# modFOC-Sensing.net
KiCad netlist of a schematic drawn in Altium Designer
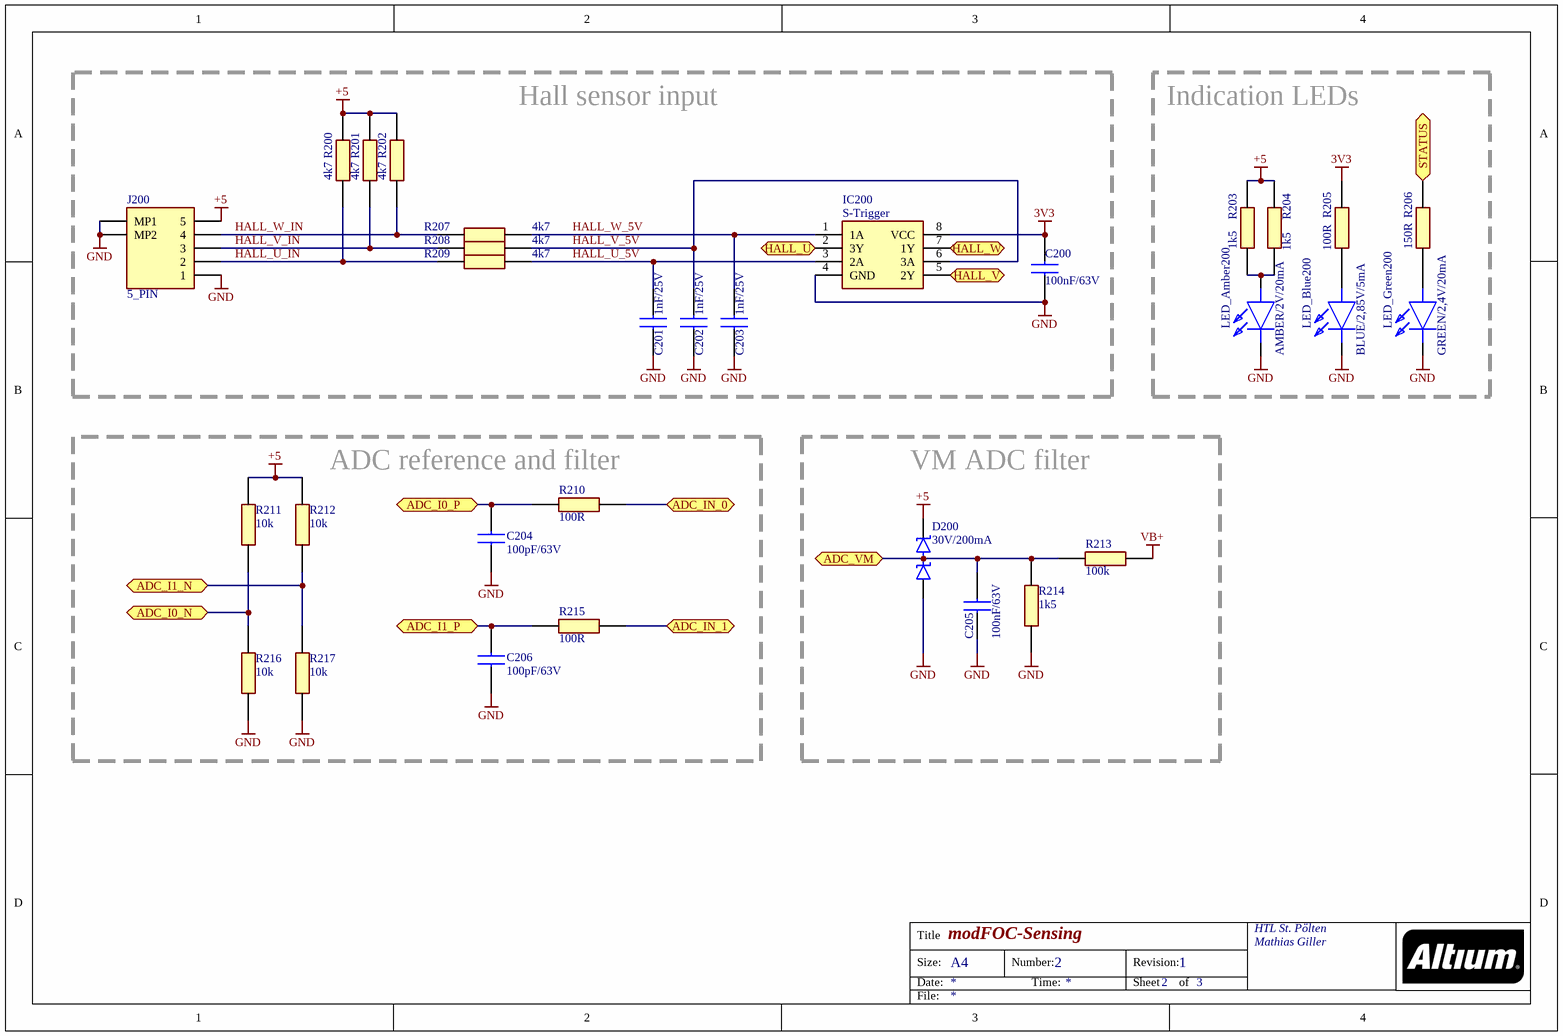
[diagram p0: modFOC-Sensing.SchDoc]

(export (version "E")
  (design (tool "Eeschema 10.0.6"))
  (components
    (comp (ref "C200")
      (value "100nF/63V")
      (footprint "CAPC1608X97N")
      (description "Capacitor")
      (fields
        (field (name "MANUFACTURER_PART_NUMBER") "VJ0603Y104JXJAC")
        (field (name "MOUSER PART NUMBER") "77-VJ0603Y104JXJAC")
      )
      (libsource (lib "Schlib1") (part "C0805C104MMREC7210"))
    )
    (comp (ref "C201")
      (value "1nF/25V")
      (footprint "CAPC1608X97N")
      (description "Capacitor")
      (fields
        (field (name "MANUFACTURER_PART_NUMBER") "GRM033R71E102KA01D")
        (field (name "MOUSER PART NUMBER") "81-GRM033R71E102KA1D")
      )
      (libsource (lib "Schlib1") (part "GRM033R71E102KA01D"))
    )
    (comp (ref "C202")
      (value "1nF/25V")
      (footprint "CAPC1608X97N")
      (description "Capacitor")
      (fields
        (field (name "MANUFACTURER_PART_NUMBER") "GRM033R71E102KA01D")
        (field (name "MOUSER PART NUMBER") "81-GRM033R71E102KA1D")
      )
      (libsource (lib "Schlib1") (part "GRM033R71E102KA01D"))
    )
    (comp (ref "C203")
      (value "1nF/25V")
      (footprint "CAPC1608X97N")
      (description "Capacitor")
      (fields
        (field (name "MANUFACTURER_PART_NUMBER") "GRM033R71E102KA01D")
        (field (name "MOUSER PART NUMBER") "81-GRM033R71E102KA1D")
      )
      (libsource (lib "Schlib1") (part "GRM033R71E102KA01D"))
    )
    (comp (ref "C204")
      (value "100pF/63V")
      (footprint "CAPC1608X87N")
      (description "Capacitor")
      (fields
        (field (name "MANUFACTURER_PART_NUMBER") "C0603C101K1HACTU")
        (field (name "MOUSER PART NUMBER") "80-C0603C101K1HACTU")
      )
      (libsource (lib "Schlib1") (part "C0603C101K1HACTU"))
    )
    (comp (ref "C205")
      (value "100nF/63V")
      (footprint "CAPC1608X97N")
      (description "Capacitor")
      (fields
        (field (name "MANUFACTURER_PART_NUMBER") "VJ0603Y104JXJAC")
        (field (name "MOUSER PART NUMBER") "77-VJ0603Y104JXJAC")
      )
      (libsource (lib "Schlib1") (part "C0805C104MMREC7210"))
    )
    (comp (ref "C206")
      (value "100pF/63V")
      (footprint "CAPC1608X87N")
      (description "Capacitor")
      (fields
        (field (name "MANUFACTURER_PART_NUMBER") "C0603C101K1HACTU")
        (field (name "MOUSER PART NUMBER") "80-C0603C101K1HACTU")
      )
      (libsource (lib "Schlib1") (part "C0603C101K1HACTU"))
    )
    (comp (ref "D200")
      (value "30V/200mA")
      (footprint "SOT95P240X110-3N")
      (description "Schottky Diode")
      (fields
        (field (name "MANUFACTURER_PART_NUMBER") "BAT54S")
        (field (name "MOUSER PART NUMBER") "583-BAT54S")
      )
      (libsource (lib "Schlib1") (part "BAT54S"))
    )
    (comp (ref "IC200")
      (value "S-Trigger")
      (footprint "SOP65P400X110-8N")
      (description "Integrated Circuit")
      (fields
        (field (name "MANUFACTURER_PART_NUMBER") "74LVC3G17DP,125")
        (field (name "MOUSER PART NUMBER") "771-LVC3G17DP125")
      )
      (libsource (lib "Schlib1") (part "74LVC3G17DP,125"))
    )
    (comp (ref "J200")
      (value "5_PIN")
      (footprint "DF13A5P125H21")
      (description "Connector")
      (fields
        (field (name "MANUFACTURER_PART_NUMBER") "DF13A-5P-1.25H(21)")
        (field (name "MOUSER PART NUMBER") "798-DF13A5P125H21")
      )
      (libsource (lib "Schlib1") (part "DF13A-5P-1.25H_21_"))
    )
    (comp (ref "LED_Amber200")
      (value "AMBER/2V/20mA")
      (footprint "LEDC1608X55N")
      (description "LED")
      (fields
        (field (name "MANUFACTURER_PART_NUMBER") "ASMT-RA45-AP932")
        (field (name "MOUSER PART NUMBER") "630-ASMT-RA45-AP932")
      )
      (libsource (lib "Schlib1") (part "ASMT-RA45-AP932"))
    )
    (comp (ref "LED_Blue200")
      (value "BLUE/2,85V/5mA")
      (footprint "LEDC1608X40N")
      (description "LED")
      (fields
        (field (name "MANUFACTURER_PART_NUMBER") "LB Q39G-L2OO-35-1")
        (field (name "MOUSER PART NUMBER") "720-LBQ39GL2N2351")
      )
      (libsource (lib "Schlib1") (part "LB_Q39G-L2OO-35-1"))
    )
    (comp (ref "LED_Green200")
      (value "GREEN/2,4V/20mA")
      (footprint "LGQ396PS35")
      (description "LED")
      (fields
        (field (name "MANUFACTURER_PART_NUMBER") "LG Q396-PS-35")
        (field (name "MOUSER PART NUMBER") "720-LGQ396A3964")
      )
      (libsource (lib "Schlib1") (part "LG_Q396-PS-35"))
    )
    (comp (ref "R200")
      (value "4k7")
      (footprint "RESC1608X55N")
      (description "Resistor")
      (fields
        (field (name "MANUFACTURER_PART_NUMBER") "CRCW06034K70JNEAC")
        (field (name "MOUSER PART NUMBER") "71-CRCW06034K70JNEAC")
      )
      (libsource (lib "") (part "CRCW06034K70JNEAC_1"))
    )
    (comp (ref "R201")
      (value "4k7")
      (footprint "RESC1608X55N")
      (description "Resistor")
      (fields
        (field (name "MANUFACTURER_PART_NUMBER") "CRCW06034K70JNEAC")
        (field (name "MOUSER PART NUMBER") "71-CRCW06034K70JNEAC")
      )
      (libsource (lib "") (part "CRCW06034K70JNEAC_1"))
    )
    (comp (ref "R202")
      (value "4k7")
      (footprint "RESC1608X55N")
      (description "Resistor")
      (fields
        (field (name "MANUFACTURER_PART_NUMBER") "CRCW06034K70JNEAC")
        (field (name "MOUSER PART NUMBER") "71-CRCW06034K70JNEAC")
      )
      (libsource (lib "") (part "CRCW06034K70JNEAC_1"))
    )
    (comp (ref "R203")
      (value "1k5")
      (footprint "RESC1608X55N")
      (description "Resistor")
      (fields (field (name "MANUFACTURER_PART_NUMBER") "ERJ1GNF1501C"))
      (libsource (lib "Schlib1") (part "ERJ1GNF1501C"))
    )
    (comp (ref "R204")
      (value "1k5")
      (footprint "RESC1608X55N")
      (description "Resistor")
      (fields (field (name "MANUFACTURER_PART_NUMBER") "ERJ1GNF1501C"))
      (libsource (lib "Schlib1") (part "ERJ1GNF1501C"))
    )
    (comp (ref "R205")
      (value "100R")
      (footprint "RESC1608X55N")
      (description "Resistor")
      (fields
        (field (name "MANUFACTURER_PART_NUMBER") "CRCW0603100RFKEAC")
        (field (name "MOUSER PART NUMBER") "71-CRCW0603100RFKEAC")
      )
      (libsource (lib "") (part "CRCW0603100RFKEAC_1"))
    )
    (comp (ref "R206")
      (value "150R")
      (footprint "RESC1608X55N")
      (description "Resistor")
      (fields
        (field (name "MANUFACTURER_PART_NUMBER") "SFR03EZPF1500")
        (field (name "MOUSER PART NUMBER") "755-SFR03EZPF1500")
      )
      (libsource (lib "Schlib1") (part "SFR03EZPF1500"))
    )
    (comp (ref "R207")
      (value "4k7")
      (footprint "RESC1608X55N")
      (description "Resistor")
      (fields
        (field (name "MANUFACTURER_PART_NUMBER") "CRCW06034K70JNEAC")
        (field (name "MOUSER PART NUMBER") "71-CRCW06034K70JNEAC")
      )
      (libsource (lib "Schlib1") (part "CRCW06034K70JNEAC"))
    )
    (comp (ref "R208")
      (value "4k7")
      (footprint "RESC1608X55N")
      (description "Resistor")
      (fields
        (field (name "MANUFACTURER_PART_NUMBER") "CRCW06034K70JNEAC")
        (field (name "MOUSER PART NUMBER") "71-CRCW06034K70JNEAC")
      )
      (libsource (lib "Schlib1") (part "CRCW06034K70JNEAC"))
    )
    (comp (ref "R209")
      (value "4k7")
      (footprint "RESC1608X55N")
      (description "Resistor")
      (fields
        (field (name "MANUFACTURER_PART_NUMBER") "CRCW06034K70JNEAC")
        (field (name "MOUSER PART NUMBER") "71-CRCW06034K70JNEAC")
      )
      (libsource (lib "Schlib1") (part "CRCW06034K70JNEAC"))
    )
    (comp (ref "R210")
      (value "100R")
      (footprint "RESC1608X55N")
      (description "Resistor")
      (fields
        (field (name "MANUFACTURER_PART_NUMBER") "CRCW0603100RFKEAC")
        (field (name "MOUSER PART NUMBER") "71-CRCW0603100RFKEAC")
      )
      (libsource (lib "Schlib1") (part "CRCW0603100RFKEAC"))
    )
    (comp (ref "R211")
      (value "10k")
      (footprint "RESC1608X55N")
      (description "Resistor")
      (fields
        (field (name "MANUFACTURER_PART_NUMBER") "RC0603FR-0710KL")
        (field (name "MOUSER PART NUMBER") "603-RC0603FR-0710KL")
      )
      (libsource (lib "Schlib1") (part "RC0603FR-0710KL"))
    )
    (comp (ref "R212")
      (value "10k")
      (footprint "RESC1608X55N")
      (description "Resistor")
      (fields
        (field (name "MANUFACTURER_PART_NUMBER") "RC0603FR-0710KL")
        (field (name "MOUSER PART NUMBER") "603-RC0603FR-0710KL")
      )
      (libsource (lib "") (part "RC0603FR-0710KL_1"))
    )
    (comp (ref "R213")
      (value "100k")
      (footprint "RESC1608X55N")
      (description "Resistor")
      (fields (field (name "MANUFACTURER_PART_NUMBER") "ERJ1GNF1003C"))
      (libsource (lib "Schlib1") (part "ERJ1GNF1003C"))
    )
    (comp (ref "R214")
      (value "1k5")
      (footprint "RESC1608X55N")
      (description "Resistor")
      (fields (field (name "MANUFACTURER_PART_NUMBER") "ERJ1GNF1501C"))
      (libsource (lib "Schlib1") (part "ERJ1GNF1501C"))
    )
    (comp (ref "R215")
      (value "100R")
      (footprint "RESC1608X55N")
      (description "Resistor")
      (fields
        (field (name "MANUFACTURER_PART_NUMBER") "CRCW0603100RFKEAC")
        (field (name "MOUSER PART NUMBER") "71-CRCW0603100RFKEAC")
      )
      (libsource (lib "Schlib1") (part "CRCW0603100RFKEAC"))
    )
    (comp (ref "R216")
      (value "10k")
      (footprint "RESC1608X55N")
      (description "Resistor")
      (fields
        (field (name "MANUFACTURER_PART_NUMBER") "RC0603FR-0710KL")
        (field (name "MOUSER PART NUMBER") "603-RC0603FR-0710KL")
      )
      (libsource (lib "") (part "RC0603FR-0710KL_1"))
    )
    (comp (ref "R217")
      (value "10k")
      (footprint "RESC1608X55N")
      (description "Resistor")
      (fields
        (field (name "MANUFACTURER_PART_NUMBER") "RC0603FR-0710KL")
        (field (name "MOUSER PART NUMBER") "603-RC0603FR-0710KL")
      )
      (libsource (lib "") (part "RC0603FR-0710KL_1"))
    )
  )
  (nets
    (net (code "1") (name "+5") (class "Default")
      (node (ref "D200") (pin "2") (pinfunction "K_2") (pintype "passive"))
      (node (ref "J200") (pin "5") (pinfunction "5_5") (pintype "passive"))
      (node (ref "R200") (pin "1") (pinfunction "1_1") (pintype "passive"))
      (node (ref "R201") (pin "1") (pinfunction "1_1") (pintype "passive"))
      (node (ref "R202") (pin "1") (pinfunction "1_1") (pintype "passive"))
      (node (ref "R203") (pin "2") (pinfunction "2_2") (pintype "passive"))
      (node (ref "R204") (pin "2") (pinfunction "2_2") (pintype "passive"))
      (node (ref "R211") (pin "2") (pinfunction "2_2") (pintype "passive"))
      (node (ref "R212") (pin "1") (pinfunction "1_1") (pintype "passive"))
    )
    (net (code "2") (name "/ADC_I0_N") (class "Default")
      (node (ref "R211") (pin "1") (pinfunction "1_1") (pintype "passive"))
      (node (ref "R216") (pin "1") (pinfunction "1_1") (pintype "passive"))
    )
    (net (code "3") (name "/ADC_I0_P") (class "Default")
      (node (ref "C204") (pin "2") (pinfunction "2_2") (pintype "passive"))
      (node (ref "R210") (pin "1") (pinfunction "1_1") (pintype "passive"))
    )
    (net (code "4") (name "/ADC_I1_N") (class "Default")
      (node (ref "R212") (pin "2") (pinfunction "2_2") (pintype "passive"))
      (node (ref "R217") (pin "1") (pinfunction "1_1") (pintype "passive"))
    )
    (net (code "5") (name "/ADC_I1_P") (class "Default")
      (node (ref "C206") (pin "2") (pinfunction "2_2") (pintype "passive"))
      (node (ref "R215") (pin "1") (pinfunction "1_1") (pintype "passive"))
    )
    (net (code "6") (name "/ADC_IN_0") (class "Default")
      (node (ref "R210") (pin "2") (pinfunction "2_2") (pintype "passive"))
    )
    (net (code "7") (name "/ADC_IN_1") (class "Default")
      (node (ref "R215") (pin "2") (pinfunction "2_2") (pintype "passive"))
    )
    (net (code "8") (name "/ADC_VM") (class "Default")
      (node (ref "C205") (pin "2") (pinfunction "2_2") (pintype "passive"))
      (node (ref "D200") (pin "3") (pinfunction "A/K_3") (pintype "passive"))
      (node (ref "R213") (pin "1") (pinfunction "1_1") (pintype "passive"))
      (node (ref "R214") (pin "2") (pinfunction "2_2") (pintype "passive"))
    )
    (net (code "9") (name "/HALL_U") (class "Default")
      (node (ref "IC200") (pin "2") (pinfunction "3Y_2") (pintype "passive"))
    )
    (net (code "10") (name "/HALL_U_5V") (class "Default")
      (node (ref "C201") (pin "1") (pinfunction "1_1") (pintype "passive"))
      (node (ref "IC200") (pin "3") (pinfunction "2A_3") (pintype "passive"))
      (node (ref "R209") (pin "2") (pinfunction "2_2") (pintype "passive"))
    )
    (net (code "11") (name "/HALL_U_IN") (class "Default")
      (node (ref "J200") (pin "2") (pinfunction "2_2") (pintype "passive"))
      (node (ref "R200") (pin "2") (pinfunction "2_2") (pintype "passive"))
      (node (ref "R209") (pin "1") (pinfunction "1_1") (pintype "passive"))
    )
    (net (code "12") (name "/HALL_V") (class "Default")
      (node (ref "IC200") (pin "5") (pinfunction "2Y_5") (pintype "passive"))
    )
    (net (code "13") (name "/HALL_V_5V") (class "Default")
      (node (ref "C202") (pin "1") (pinfunction "1_1") (pintype "passive"))
      (node (ref "IC200") (pin "6") (pinfunction "3A_6") (pintype "passive"))
      (node (ref "R208") (pin "2") (pinfunction "2_2") (pintype "passive"))
    )
    (net (code "14") (name "/HALL_V_IN") (class "Default")
      (node (ref "J200") (pin "3") (pinfunction "3_3") (pintype "passive"))
      (node (ref "R201") (pin "2") (pinfunction "2_2") (pintype "passive"))
      (node (ref "R208") (pin "1") (pinfunction "1_1") (pintype "passive"))
    )
    (net (code "15") (name "/HALL_W") (class "Default")
      (node (ref "IC200") (pin "7") (pinfunction "1Y_7") (pintype "passive"))
    )
    (net (code "16") (name "/HALL_W_5V") (class "Default")
      (node (ref "C203") (pin "1") (pinfunction "1_1") (pintype "passive"))
      (node (ref "IC200") (pin "1") (pinfunction "1A_1") (pintype "passive"))
      (node (ref "R207") (pin "2") (pinfunction "2_2") (pintype "passive"))
    )
    (net (code "17") (name "/HALL_W_IN") (class "Default")
      (node (ref "J200") (pin "4") (pinfunction "4_4") (pintype "passive"))
      (node (ref "R202") (pin "2") (pinfunction "2_2") (pintype "passive"))
      (node (ref "R207") (pin "1") (pinfunction "1_1") (pintype "passive"))
    )
    (net (code "18") (name "/STATUS") (class "Default")
      (node (ref "R206") (pin "2") (pinfunction "2_2") (pintype "passive"))
    )
    (net (code "19") (name "3V3") (class "Default")
      (node (ref "C200") (pin "2") (pinfunction "2_2") (pintype "passive"))
      (node (ref "IC200") (pin "8") (pinfunction "VCC_8") (pintype "passive"))
      (node (ref "R205") (pin "2") (pinfunction "2_2") (pintype "passive"))
    )
    (net (code "20") (name "GND") (class "Default")
      (node (ref "C200") (pin "1") (pinfunction "1_1") (pintype "passive"))
      (node (ref "C201") (pin "2") (pinfunction "2_2") (pintype "passive"))
      (node (ref "C202") (pin "2") (pinfunction "2_2") (pintype "passive"))
      (node (ref "C203") (pin "2") (pinfunction "2_2") (pintype "passive"))
      (node (ref "C204") (pin "1") (pinfunction "1_1") (pintype "passive"))
      (node (ref "C205") (pin "1") (pinfunction "1_1") (pintype "passive"))
      (node (ref "C206") (pin "1") (pinfunction "1_1") (pintype "passive"))
      (node (ref "D200") (pin "1") (pinfunction "A_1") (pintype "passive"))
      (node (ref "IC200") (pin "4") (pinfunction "GND_4") (pintype "passive"))
      (node (ref "J200") (pin "1") (pinfunction "1_1") (pintype "passive"))
      (node (ref "J200") (pin "MP1") (pinfunction "MP1_MP1") (pintype "passive"))
      (node (ref "J200") (pin "MP2") (pinfunction "MP2_MP2") (pintype "passive"))
      (node (ref "LED_Amber200") (pin "1") (pinfunction "K_1") (pintype "passive"))
      (node (ref "LED_Blue200") (pin "1") (pinfunction "K_1") (pintype "passive"))
      (node (ref "LED_Green200") (pin "1") (pinfunction "K_1") (pintype "passive"))
      (node (ref "R214") (pin "1") (pinfunction "1_1") (pintype "passive"))
      (node (ref "R216") (pin "2") (pinfunction "2_2") (pintype "passive"))
      (node (ref "R217") (pin "2") (pinfunction "2_2") (pintype "passive"))
    )
    (net (code "21") (name "Net-(LED_Amber200-A)") (class "Default")
      (node (ref "LED_Amber200") (pin "2") (pinfunction "A_2") (pintype "passive"))
      (node (ref "R203") (pin "1") (pinfunction "1_1") (pintype "passive"))
      (node (ref "R204") (pin "1") (pinfunction "1_1") (pintype "passive"))
    )
    (net (code "22") (name "Net-(LED_Blue200-A)") (class "Default")
      (node (ref "LED_Blue200") (pin "2") (pinfunction "A_2") (pintype "passive"))
      (node (ref "R205") (pin "1") (pinfunction "1_1") (pintype "passive"))
    )
    (net (code "23") (name "Net-(LED_Green200-A)") (class "Default")
      (node (ref "LED_Green200") (pin "2") (pinfunction "A_2") (pintype "passive"))
      (node (ref "R206") (pin "1") (pinfunction "1_1") (pintype "passive"))
    )
    (net (code "24") (name "VB+") (class "Default")
      (node (ref "R213") (pin "2") (pinfunction "2_2") (pintype "passive"))
    )
  )
)
